# ethernet_switch_single.net
KiCad netlist of a schematic drawn in EAGLE
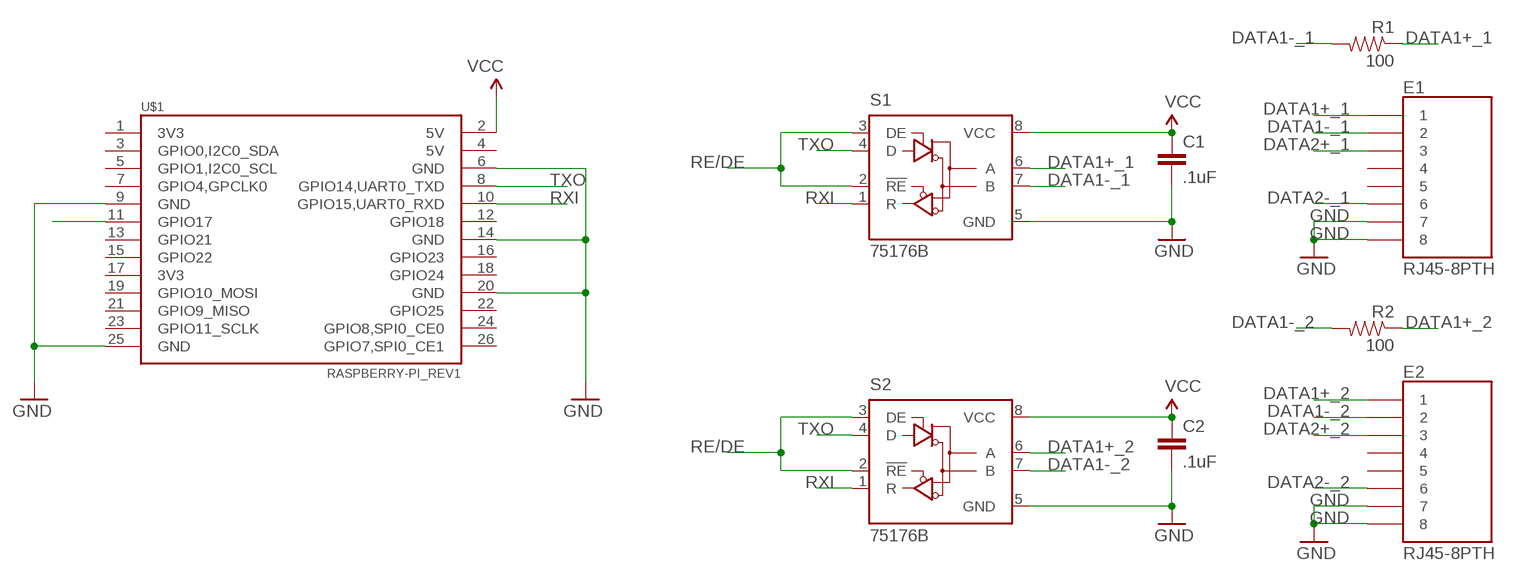
[diagram p0: schematic, sheet 1]

(export (version "E")
  (design (tool "Eeschema 10.0.6"))
  (components
    (comp (ref "C1")
      (value ".1uF")
      (footprint "eagle-import:0402-CAP")
      (libsource (lib "eagle-import") (part "CAP0402-CAP"))
    )
    (comp (ref "C2")
      (value ".1uF")
      (footprint "eagle-import:0402-CAP")
      (libsource (lib "eagle-import") (part "CAP0402-CAP"))
    )
    (comp (ref "E1")
      (value "RJ45-8PTH")
      (footprint "eagle-import:RJ45-8")
      (libsource (lib "eagle-import") (part "RJ45-8PTH"))
    )
    (comp (ref "E2")
      (value "RJ45-8PTH")
      (footprint "eagle-import:RJ45-8")
      (libsource (lib "eagle-import") (part "RJ45-8PTH"))
    )
    (comp (ref "R1")
      (value "100")
      (footprint "eagle-import:1206")
      (libsource (lib "eagle-import") (part "RESISTOR1206"))
    )
    (comp (ref "R2")
      (value "100")
      (footprint "eagle-import:1206")
      (libsource (lib "eagle-import") (part "RESISTOR1206"))
    )
    (comp (ref "S1")
      (value "75176B")
      (footprint "eagle-import:D_R-PDSO-G8")
      (libsource (lib "eagle-import") (part "75176B"))
    )
    (comp (ref "S2")
      (value "75176B")
      (footprint "eagle-import:D_R-PDSO-G8")
      (libsource (lib "eagle-import") (part "75176B"))
    )
    (comp (ref "U$1")
      (value "RASPBERRY-PI_REV1")
      (footprint "eagle-import:RASPBERRY-PI_REV1")
      (libsource (lib "eagle-import") (part "RASPBERRY-PI_REV1"))
    )
  )
  (nets
    (net (code "1") (name "/DATA1+_1") (class "Default")
      (node (ref "E1") (pin "1") (pinfunction "1_1") (pintype "bidirectional"))
      (node (ref "R1") (pin "1") (pinfunction "1_1") (pintype "passive"))
      (node (ref "S1") (pin "6") (pinfunction "A_6") (pintype "output"))
    )
    (net (code "2") (name "/DATA1+_2") (class "Default")
      (node (ref "E2") (pin "1") (pinfunction "1_1") (pintype "bidirectional"))
      (node (ref "R2") (pin "1") (pinfunction "1_1") (pintype "passive"))
      (node (ref "S2") (pin "6") (pinfunction "A_6") (pintype "output"))
    )
    (net (code "3") (name "/DATA1-_1") (class "Default")
      (node (ref "E1") (pin "2") (pinfunction "2_2") (pintype "bidirectional"))
      (node (ref "R1") (pin "2") (pinfunction "2_2") (pintype "passive"))
      (node (ref "S1") (pin "7") (pinfunction "B_7") (pintype "output"))
    )
    (net (code "4") (name "/DATA1-_2") (class "Default")
      (node (ref "E2") (pin "2") (pinfunction "2_2") (pintype "bidirectional"))
      (node (ref "R2") (pin "2") (pinfunction "2_2") (pintype "passive"))
      (node (ref "S2") (pin "7") (pinfunction "B_7") (pintype "output"))
    )
    (net (code "5") (name "/DATA2+_1") (class "Default")
      (node (ref "E1") (pin "3") (pinfunction "3_3") (pintype "bidirectional"))
    )
    (net (code "6") (name "/DATA2+_2") (class "Default")
      (node (ref "E2") (pin "3") (pinfunction "3_3") (pintype "bidirectional"))
    )
    (net (code "7") (name "/DATA2-_1") (class "Default")
      (node (ref "E1") (pin "6") (pinfunction "6_6") (pintype "bidirectional"))
    )
    (net (code "8") (name "/DATA2-_2") (class "Default")
      (node (ref "E2") (pin "6") (pinfunction "6_6") (pintype "bidirectional"))
    )
    (net (code "9") (name "/RE{slash}DE") (class "Default")
      (node (ref "S1") (pin "2") (pinfunction "~{RE}_2") (pintype "input"))
      (node (ref "S1") (pin "3") (pinfunction "DE_3") (pintype "input"))
      (node (ref "S2") (pin "2") (pinfunction "~{RE}_2") (pintype "input"))
      (node (ref "S2") (pin "3") (pinfunction "DE_3") (pintype "input"))
      (node (ref "U$1") (pin "11") (pinfunction "GPIO17_11") (pintype "bidirectional"))
    )
    (net (code "10") (name "/RXI") (class "Default")
      (node (ref "S1") (pin "1") (pinfunction "R_1") (pintype "input"))
      (node (ref "S2") (pin "1") (pinfunction "R_1") (pintype "input"))
      (node (ref "U$1") (pin "10") (pinfunction "GPIO15,UART0_RXD_10") (pintype "bidirectional"))
    )
    (net (code "11") (name "/TXO") (class "Default")
      (node (ref "S1") (pin "4") (pinfunction "D_4") (pintype "input"))
      (node (ref "S2") (pin "4") (pinfunction "D_4") (pintype "input"))
      (node (ref "U$1") (pin "8") (pinfunction "GPIO14,UART0_TXD_8") (pintype "bidirectional"))
    )
    (net (code "12") (name "GND") (class "Default")
      (node (ref "C1") (pin "2") (pinfunction "2_2") (pintype "passive"))
      (node (ref "C2") (pin "2") (pinfunction "2_2") (pintype "passive"))
      (node (ref "E1") (pin "7") (pinfunction "7_7") (pintype "bidirectional"))
      (node (ref "E1") (pin "8") (pinfunction "8_8") (pintype "bidirectional"))
      (node (ref "E2") (pin "7") (pinfunction "7_7") (pintype "bidirectional"))
      (node (ref "E2") (pin "8") (pinfunction "8_8") (pintype "bidirectional"))
      (node (ref "S1") (pin "5") (pinfunction "GND_5") (pintype "power_in"))
      (node (ref "S2") (pin "5") (pinfunction "GND_5") (pintype "power_in"))
      (node (ref "U$1") (pin "14") (pinfunction "GND_14") (pintype "bidirectional"))
      (node (ref "U$1") (pin "20") (pinfunction "GND_20") (pintype "bidirectional"))
      (node (ref "U$1") (pin "25") (pinfunction "GND_25") (pintype "bidirectional"))
      (node (ref "U$1") (pin "6") (pinfunction "GND_6") (pintype "bidirectional"))
      (node (ref "U$1") (pin "9") (pinfunction "GND_9") (pintype "bidirectional"))
    )
    (net (code "13") (name "VCC") (class "Default")
      (node (ref "C1") (pin "1") (pinfunction "1_1") (pintype "passive"))
      (node (ref "C2") (pin "1") (pinfunction "1_1") (pintype "passive"))
      (node (ref "S1") (pin "8") (pinfunction "VCC_8") (pintype "power_in"))
      (node (ref "S2") (pin "8") (pinfunction "VCC_8") (pintype "power_in"))
      (node (ref "U$1") (pin "2") (pinfunction "5V_2") (pintype "bidirectional"))
    )
    (net (code "14") (name "unconnected-(E1-Pad4)") (class "Default")
      (node (ref "E1") (pin "4") (pinfunction "4_4") (pintype "bidirectional"))
    )
    (net (code "15") (name "unconnected-(E1-Pad5)") (class "Default")
      (node (ref "E1") (pin "5") (pinfunction "5_5") (pintype "bidirectional"))
    )
    (net (code "16") (name "unconnected-(E2-Pad4)") (class "Default")
      (node (ref "E2") (pin "4") (pinfunction "4_4") (pintype "bidirectional"))
    )
    (net (code "17") (name "unconnected-(E2-Pad5)") (class "Default")
      (node (ref "E2") (pin "5") (pinfunction "5_5") (pintype "bidirectional"))
    )
    (net (code "18") (name "unconnected-(U$1-3V3-Pad1)") (class "Default")
      (node (ref "U$1") (pin "1") (pinfunction "3V3_1") (pintype "bidirectional"))
    )
    (net (code "19") (name "unconnected-(U$1-3V3-Pad17)") (class "Default")
      (node (ref "U$1") (pin "17") (pinfunction "3V3_17") (pintype "bidirectional"))
    )
    (net (code "20") (name "unconnected-(U$1-5V-Pad4)") (class "Default")
      (node (ref "U$1") (pin "4") (pinfunction "5V_4") (pintype "bidirectional"))
    )
    (net (code "21") (name "unconnected-(U$1-GPIO0,I2C0_SDA-Pad3)") (class "Default")
      (node (ref "U$1") (pin "3") (pinfunction "GPIO0,I2C0_SDA_3") (pintype "bidirectional"))
    )
    (net (code "22") (name "unconnected-(U$1-GPIO1,I2C0_SCL-Pad5)") (class "Default")
      (node (ref "U$1") (pin "5") (pinfunction "GPIO1,I2C0_SCL_5") (pintype "bidirectional"))
    )
    (net (code "23") (name "unconnected-(U$1-GPIO4,GPCLK0-Pad7)") (class "Default")
      (node (ref "U$1") (pin "7") (pinfunction "GPIO4,GPCLK0_7") (pintype "bidirectional"))
    )
    (net (code "24") (name "unconnected-(U$1-GPIO7,SPI0_CE1-Pad26)") (class "Default")
      (node (ref "U$1") (pin "26") (pinfunction "GPIO7,SPI0_CE1_26") (pintype "bidirectional"))
    )
    (net (code "25") (name "unconnected-(U$1-GPIO8,SPI0_CE0-Pad24)") (class "Default")
      (node (ref "U$1") (pin "24") (pinfunction "GPIO8,SPI0_CE0_24") (pintype "bidirectional"))
    )
    (net (code "26") (name "unconnected-(U$1-GPIO9_MISO-Pad21)") (class "Default")
      (node (ref "U$1") (pin "21") (pinfunction "GPIO9_MISO_21") (pintype "bidirectional"))
    )
    (net (code "27") (name "unconnected-(U$1-GPIO10_MOSI-Pad19)") (class "Default")
      (node (ref "U$1") (pin "19") (pinfunction "GPIO10_MOSI_19") (pintype "bidirectional"))
    )
    (net (code "28") (name "unconnected-(U$1-GPIO11_SCLK-Pad23)") (class "Default")
      (node (ref "U$1") (pin "23") (pinfunction "GPIO11_SCLK_23") (pintype "bidirectional"))
    )
    (net (code "29") (name "unconnected-(U$1-GPIO18-Pad12)") (class "Default")
      (node (ref "U$1") (pin "12") (pinfunction "GPIO18_12") (pintype "bidirectional"))
    )
    (net (code "30") (name "unconnected-(U$1-GPIO21-Pad13)") (class "Default")
      (node (ref "U$1") (pin "13") (pinfunction "GPIO21_13") (pintype "bidirectional"))
    )
    (net (code "31") (name "unconnected-(U$1-GPIO22-Pad15)") (class "Default")
      (node (ref "U$1") (pin "15") (pinfunction "GPIO22_15") (pintype "bidirectional"))
    )
    (net (code "32") (name "unconnected-(U$1-GPIO23-Pad16)") (class "Default")
      (node (ref "U$1") (pin "16") (pinfunction "GPIO23_16") (pintype "bidirectional"))
    )
    (net (code "33") (name "unconnected-(U$1-GPIO24-Pad18)") (class "Default")
      (node (ref "U$1") (pin "18") (pinfunction "GPIO24_18") (pintype "bidirectional"))
    )
    (net (code "34") (name "unconnected-(U$1-GPIO25-Pad22)") (class "Default")
      (node (ref "U$1") (pin "22") (pinfunction "GPIO25_22") (pintype "bidirectional"))
    )
  )
)
